# Jamali.net
KiCad netlist of a schematic drawn in Altium Designer
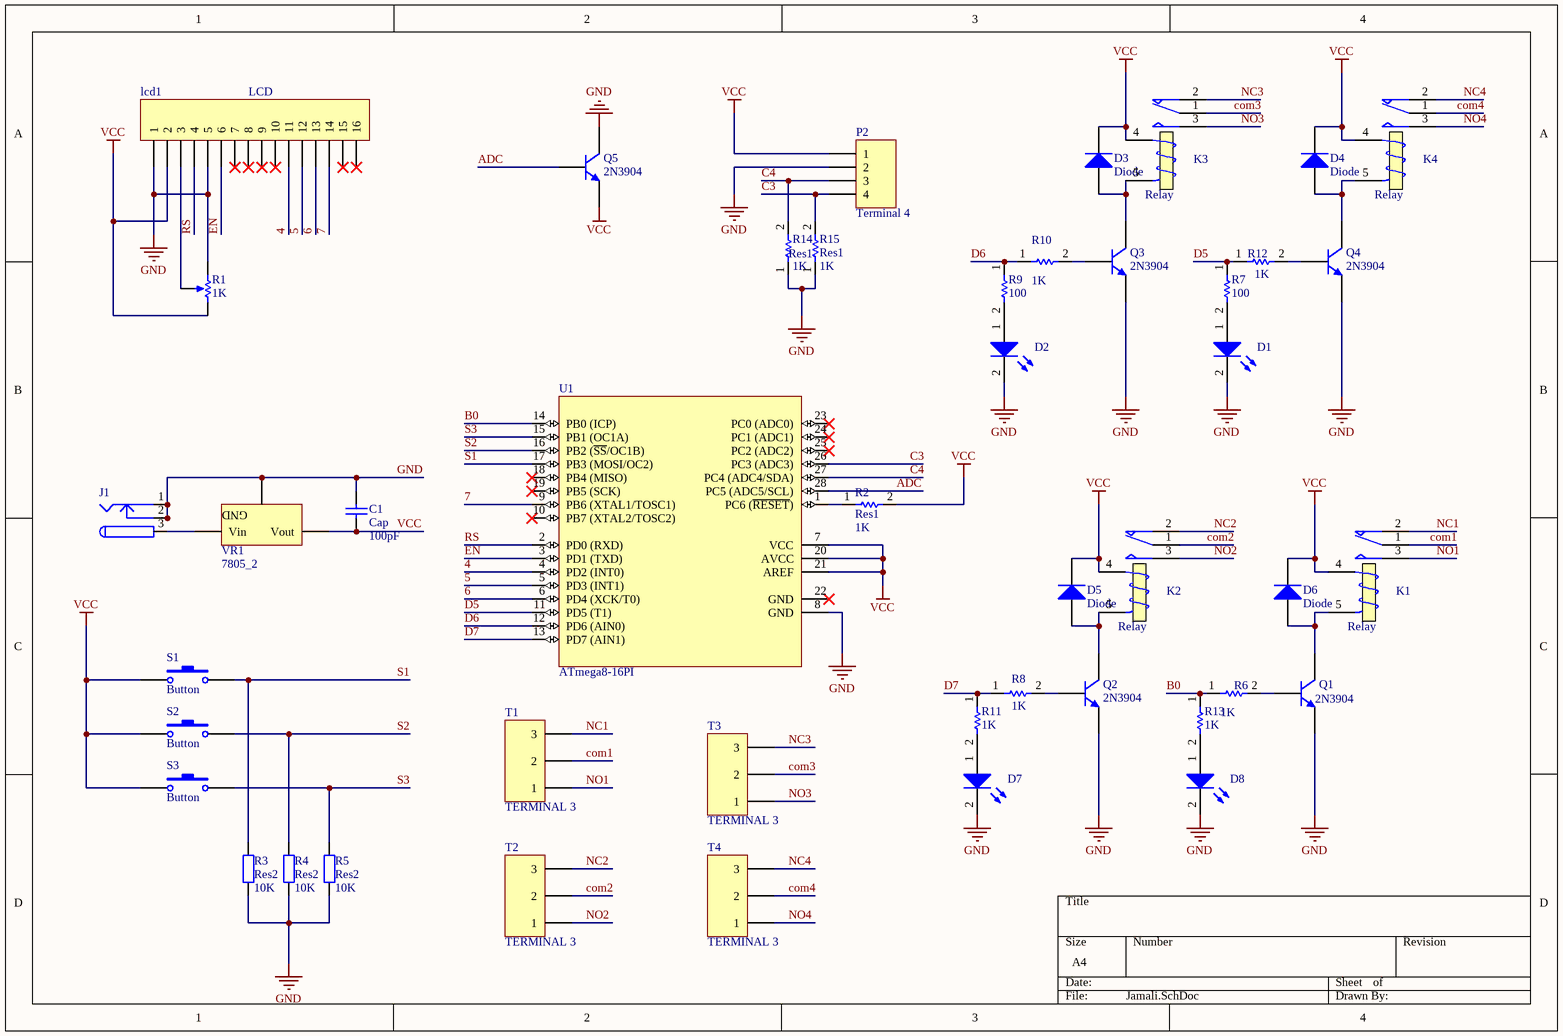
[diagram p0: Jamali.SchDoc]

(export (version "E")
  (design (tool "Eeschema 10.0.6"))
  (components
    (comp (ref "C1")
      (value "Cap")
      (footprint "C2.5-3")
      (description "Capacitor")
      (fields (field (name "ALTIUM_VALUE") "100pF") (field (name "PUBLISHER") "Altium Limited"))
      (libsource (lib "MYLIB") (part "Cap"))
    )
    (comp (ref "D1")
      (value "LED0")
      (footprint "LED3MM")
      (description "Typical INFRARED GaAs LED")
      (fields (field (name "PUBLISHER") "Altium Limited"))
      (libsource (lib "MYLIB") (part "LED0"))
    )
    (comp (ref "D2")
      (value "LED0")
      (footprint "LED3MM")
      (description "Typical INFRARED GaAs LED")
      (fields (field (name "PUBLISHER") "Altium Limited"))
      (libsource (lib "MYLIB") (part "LED0"))
    )
    (comp (ref "D3")
      (value "Diode")
      (footprint "DO35-7")
      (fields (field (name "PUBLISHER") "Altium Limited"))
      (libsource (lib "MYLIB") (part "Diode"))
    )
    (comp (ref "D4")
      (value "Diode")
      (footprint "DO35-7")
      (fields (field (name "PUBLISHER") "Altium Limited"))
      (libsource (lib "MYLIB") (part "Diode"))
    )
    (comp (ref "D5")
      (value "Diode")
      (footprint "DO35-7")
      (fields (field (name "PUBLISHER") "Altium Limited"))
      (libsource (lib "MYLIB") (part "Diode"))
    )
    (comp (ref "D6")
      (value "Diode")
      (footprint "DO35-7")
      (fields (field (name "PUBLISHER") "Altium Limited"))
      (libsource (lib "MYLIB") (part "Diode"))
    )
    (comp (ref "D7")
      (value "LED0")
      (footprint "LED3MM")
      (description "Typical INFRARED GaAs LED")
      (fields (field (name "PUBLISHER") "Altium Limited"))
      (libsource (lib "MYLIB") (part "LED0"))
    )
    (comp (ref "D8")
      (value "LED0")
      (footprint "LED3MM")
      (description "Typical INFRARED GaAs LED")
      (fields (field (name "PUBLISHER") "Altium Limited"))
      (libsource (lib "MYLIB") (part "LED0"))
    )
    (comp (ref "J1")
      (value "~")
      (footprint "jack")
      (description "Low Voltage Power Supply Connector")
      (fields (field (name "PUBLISHER") "Altium Limited"))
      (libsource (lib "MYLIB") (part "Jack"))
    )
    (comp (ref "K1")
      (value "Relay")
      (footprint "ZF112")
      (description "SPDT Relay")
      (fields (field (name "PUBLISHER") "Altium Limited"))
      (libsource (lib "MYLIB") (part "Relay"))
    )
    (comp (ref "K2")
      (value "Relay")
      (footprint "ZF112")
      (description "SPDT Relay")
      (fields (field (name "PUBLISHER") "Altium Limited"))
      (libsource (lib "MYLIB") (part "Relay"))
    )
    (comp (ref "K3")
      (value "Relay")
      (footprint "ZF112")
      (description "SPDT Relay")
      (fields (field (name "PUBLISHER") "Altium Limited"))
      (libsource (lib "MYLIB") (part "Relay"))
    )
    (comp (ref "K4")
      (value "Relay")
      (footprint "ZF112")
      (description "SPDT Relay")
      (fields (field (name "PUBLISHER") "Altium Limited"))
      (libsource (lib "MYLIB") (part "Relay"))
    )
    (comp (ref "lcd1")
      (value "LCD")
      (footprint "TUXGR_16X2_R2")
      (fields (field (name "PUBLISHER") "Altium Limited"))
      (libsource (lib "MYLIB") (part "LCD"))
    )
    (comp (ref "P2")
      (value "Terminal 4")
      (footprint "AK500/4-H")
      (description "Header, 4-Pin")
      (fields (field (name "PUBLISHER") "Altium Limited"))
      (libsource (lib "MYLIB") (part "Terminal 4"))
    )
    (comp (ref "Q1")
      (value "2N3904")
      (footprint "TO92D")
      (description "NPN General Purpose Amplifier")
      (fields (field (name "PUBLISHER") "Altium Limited"))
      (libsource (lib "MYLIB") (part "2N3904"))
    )
    (comp (ref "Q2")
      (value "2N3904")
      (footprint "TO92D")
      (description "NPN General Purpose Amplifier")
      (fields (field (name "PUBLISHER") "Altium Limited"))
      (libsource (lib "MYLIB") (part "2N3904"))
    )
    (comp (ref "Q3")
      (value "2N3904")
      (footprint "TO92D")
      (description "NPN General Purpose Amplifier")
      (fields (field (name "PUBLISHER") "Altium Limited"))
      (libsource (lib "MYLIB") (part "2N3904"))
    )
    (comp (ref "Q4")
      (value "2N3904")
      (footprint "TO92D")
      (description "NPN General Purpose Amplifier")
      (fields (field (name "PUBLISHER") "Altium Limited"))
      (libsource (lib "MYLIB") (part "2N3904"))
    )
    (comp (ref "Q5")
      (value "2N3904")
      (footprint "TO92D")
      (description "NPN General Purpose Amplifier")
      (fields (field (name "PUBLISHER") "Altium Limited"))
      (libsource (lib "MYLIB") (part "2N3904"))
    )
    (comp (ref "R1")
      (value "1K")
      (footprint "Pot_2")
      (description "Potentiometer")
      (fields (field (name "PUBLISHER") "Altium Limited"))
      (libsource (lib "MYLIB") (part "pot_2"))
    )
    (comp (ref "R2")
      (value "Res1")
      (footprint "0204/7")
      (description "Resistor")
      (fields (field (name "ALTIUM_VALUE") "1K") (field (name "PUBLISHER") "Altium Limited"))
      (libsource (lib "MYLIB") (part "Res1"))
    )
    (comp (ref "R3")
      (value "Res2")
      (footprint "0204/7")
      (description "Resistor")
      (fields (field (name "ALTIUM_VALUE") "10K") (field (name "PUBLISHER") "Altium Limited"))
      (libsource (lib "Miscellaneous Devices") (part "Res2"))
    )
    (comp (ref "R4")
      (value "Res2")
      (footprint "0204/7")
      (description "Resistor")
      (fields (field (name "ALTIUM_VALUE") "10K") (field (name "PUBLISHER") "Altium Limited"))
      (libsource (lib "Miscellaneous Devices") (part "Res2"))
    )
    (comp (ref "R5")
      (value "Res2")
      (footprint "0204/7")
      (description "Resistor")
      (fields (field (name "ALTIUM_VALUE") "10K") (field (name "PUBLISHER") "Altium Limited"))
      (libsource (lib "Miscellaneous Devices") (part "Res2"))
    )
    (comp (ref "R6")
      (value "1K")
      (footprint "0204/7")
      (description "Resistor")
      (fields (field (name "Comment") "Res1") (field (name "PUBLISHER") "Altium Limited"))
      (libsource (lib "MYLIB") (part "Res1"))
    )
    (comp (ref "R7")
      (value "100")
      (footprint "0204/7")
      (description "Resistor")
      (fields (field (name "Comment") "Res1") (field (name "PUBLISHER") "Altium Limited"))
      (libsource (lib "MYLIB") (part "Res1"))
    )
    (comp (ref "R8")
      (value "1K")
      (footprint "0204/7")
      (description "Resistor")
      (fields (field (name "Comment") "Res1") (field (name "PUBLISHER") "Altium Limited"))
      (libsource (lib "MYLIB") (part "Res1"))
    )
    (comp (ref "R9")
      (value "100")
      (footprint "0204/7")
      (description "Resistor")
      (fields (field (name "Comment") "Res1") (field (name "PUBLISHER") "Altium Limited"))
      (libsource (lib "MYLIB") (part "Res1"))
    )
    (comp (ref "R10")
      (value "1K")
      (footprint "0204/7")
      (description "Resistor")
      (fields (field (name "Comment") "Res1") (field (name "PUBLISHER") "Altium Limited"))
      (libsource (lib "MYLIB") (part "Res1"))
    )
    (comp (ref "R11")
      (value "1K")
      (footprint "0204/7")
      (description "Resistor")
      (fields (field (name "Comment") "Res1") (field (name "PUBLISHER") "Altium Limited"))
      (libsource (lib "MYLIB") (part "Res1"))
    )
    (comp (ref "R12")
      (value "1K")
      (footprint "0204/7")
      (description "Resistor")
      (fields (field (name "Comment") "Res1") (field (name "PUBLISHER") "Altium Limited"))
      (libsource (lib "MYLIB") (part "Res1"))
    )
    (comp (ref "R13")
      (value "1K")
      (footprint "0204/7")
      (description "Resistor")
      (fields (field (name "Comment") "Res1") (field (name "PUBLISHER") "Altium Limited"))
      (libsource (lib "MYLIB") (part "Res1"))
    )
    (comp (ref "R14")
      (value "Res1")
      (footprint "0204/7")
      (description "Resistor")
      (fields (field (name "ALTIUM_VALUE") "1K") (field (name "PUBLISHER") "Altium Limited"))
      (libsource (lib "MYLIB") (part "Res1"))
    )
    (comp (ref "R15")
      (value "Res1")
      (footprint "0204/7")
      (description "Resistor")
      (fields (field (name "ALTIUM_VALUE") "1K") (field (name "PUBLISHER") "Altium Limited"))
      (libsource (lib "MYLIB") (part "Res1"))
    )
    (comp (ref "S1")
      (value "Button")
      (footprint "B3F-10XX")
      (description "Switch")
      (fields (field (name "PUBLISHER") "Altium Limited"))
      (libsource (lib "MYLIB") (part "Button"))
    )
    (comp (ref "S2")
      (value "Button")
      (footprint "B3F-10XX")
      (description "Switch")
      (fields (field (name "PUBLISHER") "Altium Limited"))
      (libsource (lib "MYLIB") (part "Button"))
    )
    (comp (ref "S3")
      (value "Button")
      (footprint "B3F-10XX")
      (description "Switch")
      (fields (field (name "PUBLISHER") "Altium Limited"))
      (libsource (lib "MYLIB") (part "Button"))
    )
    (comp (ref "T1")
      (value "TERMINAL 3")
      (footprint "AK500/3-H")
      (fields (field (name "PUBLISHER") "Altium Limited"))
      (libsource (lib "MYLIB") (part "TERMINAL 3"))
    )
    (comp (ref "T2")
      (value "TERMINAL 3")
      (footprint "AK500/3-H")
      (fields (field (name "PUBLISHER") "Altium Limited"))
      (libsource (lib "MYLIB") (part "TERMINAL 3"))
    )
    (comp (ref "T3")
      (value "TERMINAL 3")
      (footprint "AK500/3-H")
      (fields (field (name "PUBLISHER") "Altium Limited"))
      (libsource (lib "MYLIB") (part "TERMINAL 3"))
    )
    (comp (ref "T4")
      (value "TERMINAL 3")
      (footprint "AK500/3-H")
      (fields (field (name "PUBLISHER") "Altium Limited"))
      (libsource (lib "MYLIB") (part "TERMINAL 3"))
    )
    (comp (ref "U1")
      (value "ATmega8-16PI")
      (footprint "DIL28-3")
      (description "8-Bit AVR Microcontroller with 8K Bytes of In-System Programmable Flash Memory")
      (fields (field (name "PUBLISHER") "Altium Limited"))
      (libsource (lib "MYLIB") (part "ATmega8-16PI"))
    )
    (comp (ref "VR1")
      (value "7805_2")
      (footprint "TO220H")
      (description "Voltage Regulator")
      (fields (field (name "PUBLISHER") "Altium Limited"))
      (libsource (lib "MYLIB") (part "7805_2"))
    )
  )
  (nets
    (net (code "1") (name "/4") (class "Default")
      (node (ref "U1") (pin "4") (pinfunction "PD2_(INT0)_4") (pintype "bidirectional"))
      (node (ref "lcd1") (pin "11") (pinfunction "11_11") (pintype "passive"))
    )
    (net (code "2") (name "/5") (class "Default")
      (node (ref "U1") (pin "5") (pinfunction "PD3_(INT1)_5") (pintype "bidirectional"))
      (node (ref "lcd1") (pin "12") (pinfunction "12_12") (pintype "passive"))
    )
    (net (code "3") (name "/6") (class "Default")
      (node (ref "U1") (pin "6") (pinfunction "PD4_(XCK/T0)_6") (pintype "bidirectional"))
      (node (ref "lcd1") (pin "13") (pinfunction "13_13") (pintype "passive"))
    )
    (net (code "4") (name "/7") (class "Default")
      (node (ref "U1") (pin "9") (pinfunction "PB6_(XTAL1/TOSC1)_9") (pintype "bidirectional"))
      (node (ref "lcd1") (pin "14") (pinfunction "14_14") (pintype "passive"))
    )
    (net (code "5") (name "/ADC") (class "Default")
      (node (ref "Q5") (pin "B") (pinfunction "B_B") (pintype "passive"))
      (node (ref "U1") (pin "28") (pinfunction "PC5_(ADC5/SCL)_28") (pintype "bidirectional"))
    )
    (net (code "6") (name "/B0") (class "Default")
      (node (ref "R13") (pin "1") (pinfunction "1_1") (pintype "passive"))
      (node (ref "R6") (pin "1") (pinfunction "1_1") (pintype "passive"))
      (node (ref "U1") (pin "14") (pinfunction "PB0_(ICP)_14") (pintype "bidirectional"))
    )
    (net (code "7") (name "/C3") (class "Default")
      (node (ref "P2") (pin "4") (pinfunction "4_4") (pintype "passive"))
      (node (ref "R15") (pin "2") (pinfunction "2_2") (pintype "passive"))
      (node (ref "U1") (pin "26") (pinfunction "PC3_(ADC3)_26") (pintype "bidirectional"))
    )
    (net (code "8") (name "/C4") (class "Default")
      (node (ref "P2") (pin "3") (pinfunction "3_3") (pintype "passive"))
      (node (ref "R14") (pin "2") (pinfunction "2_2") (pintype "passive"))
      (node (ref "U1") (pin "27") (pinfunction "PC4_(ADC4/SDA)_27") (pintype "bidirectional"))
    )
    (net (code "9") (name "/D5") (class "Default")
      (node (ref "R12") (pin "1") (pinfunction "1_1") (pintype "passive"))
      (node (ref "R7") (pin "1") (pinfunction "1_1") (pintype "passive"))
      (node (ref "U1") (pin "11") (pinfunction "PD5_(T1)_11") (pintype "bidirectional"))
    )
    (net (code "10") (name "/D6") (class "Default")
      (node (ref "R10") (pin "1") (pinfunction "1_1") (pintype "passive"))
      (node (ref "R9") (pin "1") (pinfunction "1_1") (pintype "passive"))
      (node (ref "U1") (pin "12") (pinfunction "PD6_(AIN0)_12") (pintype "bidirectional"))
    )
    (net (code "11") (name "/D7") (class "Default")
      (node (ref "R11") (pin "1") (pinfunction "1_1") (pintype "passive"))
      (node (ref "R8") (pin "1") (pinfunction "1_1") (pintype "passive"))
      (node (ref "U1") (pin "13") (pinfunction "PD7_(AIN1)_13") (pintype "bidirectional"))
    )
    (net (code "12") (name "/EN") (class "Default")
      (node (ref "U1") (pin "3") (pinfunction "PD1_(TXD)_3") (pintype "bidirectional"))
      (node (ref "lcd1") (pin "6") (pinfunction "6_6") (pintype "passive"))
    )
    (net (code "13") (name "/NC1") (class "Default")
      (node (ref "K1") (pin "2") (pinfunction "NC_2") (pintype "passive"))
      (node (ref "T1") (pin "3") (pinfunction "3_3") (pintype "passive"))
    )
    (net (code "14") (name "/NC2") (class "Default")
      (node (ref "K2") (pin "2") (pinfunction "NC_2") (pintype "passive"))
      (node (ref "T2") (pin "3") (pinfunction "3_3") (pintype "passive"))
    )
    (net (code "15") (name "/NC3") (class "Default")
      (node (ref "K3") (pin "2") (pinfunction "NC_2") (pintype "passive"))
      (node (ref "T3") (pin "3") (pinfunction "3_3") (pintype "passive"))
    )
    (net (code "16") (name "/NC4") (class "Default")
      (node (ref "K4") (pin "2") (pinfunction "NC_2") (pintype "passive"))
      (node (ref "T4") (pin "3") (pinfunction "3_3") (pintype "passive"))
    )
    (net (code "17") (name "/NO1") (class "Default")
      (node (ref "K1") (pin "3") (pinfunction "NO_3") (pintype "passive"))
      (node (ref "T1") (pin "1") (pinfunction "1_1") (pintype "passive"))
    )
    (net (code "18") (name "/NO2") (class "Default")
      (node (ref "K2") (pin "3") (pinfunction "NO_3") (pintype "passive"))
      (node (ref "T2") (pin "1") (pinfunction "1_1") (pintype "passive"))
    )
    (net (code "19") (name "/NO3") (class "Default")
      (node (ref "K3") (pin "3") (pinfunction "NO_3") (pintype "passive"))
      (node (ref "T3") (pin "1") (pinfunction "1_1") (pintype "passive"))
    )
    (net (code "20") (name "/NO4") (class "Default")
      (node (ref "K4") (pin "3") (pinfunction "NO_3") (pintype "passive"))
      (node (ref "T4") (pin "1") (pinfunction "1_1") (pintype "passive"))
    )
    (net (code "21") (name "/RS") (class "Default")
      (node (ref "U1") (pin "2") (pinfunction "PD0_(RXD)_2") (pintype "bidirectional"))
      (node (ref "lcd1") (pin "4") (pinfunction "4_4") (pintype "passive"))
    )
    (net (code "22") (name "/S1") (class "Default")
      (node (ref "R3") (pin "2") (pinfunction "2_2") (pintype "passive"))
      (node (ref "S1") (pin "2") (pinfunction "2_2") (pintype "passive"))
      (node (ref "U1") (pin "17") (pinfunction "PB3_(MOSI/OC2)_17") (pintype "bidirectional"))
    )
    (net (code "23") (name "/S2") (class "Default")
      (node (ref "R4") (pin "2") (pinfunction "2_2") (pintype "passive"))
      (node (ref "S2") (pin "2") (pinfunction "2_2") (pintype "passive"))
      (node (ref "U1") (pin "16") (pinfunction "PB2_(~{SS}/OC1B)_16") (pintype "bidirectional"))
    )
    (net (code "24") (name "/S3") (class "Default")
      (node (ref "R5") (pin "2") (pinfunction "2_2") (pintype "passive"))
      (node (ref "S3") (pin "2") (pinfunction "2_2") (pintype "passive"))
      (node (ref "U1") (pin "15") (pinfunction "PB1_(OC1A)_15") (pintype "bidirectional"))
    )
    (net (code "25") (name "/com1") (class "Default")
      (node (ref "K1") (pin "1") (pinfunction "COM_1") (pintype "passive"))
      (node (ref "T1") (pin "2") (pinfunction "2_2") (pintype "passive"))
    )
    (net (code "26") (name "/com2") (class "Default")
      (node (ref "K2") (pin "1") (pinfunction "COM_1") (pintype "passive"))
      (node (ref "T2") (pin "2") (pinfunction "2_2") (pintype "passive"))
    )
    (net (code "27") (name "/com3") (class "Default")
      (node (ref "K3") (pin "1") (pinfunction "COM_1") (pintype "passive"))
      (node (ref "T3") (pin "2") (pinfunction "2_2") (pintype "passive"))
    )
    (net (code "28") (name "/com4") (class "Default")
      (node (ref "K4") (pin "1") (pinfunction "COM_1") (pintype "passive"))
      (node (ref "T4") (pin "2") (pinfunction "2_2") (pintype "passive"))
    )
    (net (code "29") (name "GND") (class "Default")
      (node (ref "C1") (pin "2") (pinfunction "2_2") (pintype "passive"))
      (node (ref "D1") (pin "2") (pinfunction "2_2") (pintype "passive"))
      (node (ref "D2") (pin "2") (pinfunction "2_2") (pintype "passive"))
      (node (ref "D7") (pin "2") (pinfunction "2_2") (pintype "passive"))
      (node (ref "D8") (pin "2") (pinfunction "2_2") (pintype "passive"))
      (node (ref "J1") (pin "1") (pinfunction "1_1") (pintype "power_in"))
      (node (ref "J1") (pin "2") (pinfunction "2_2") (pintype "power_in"))
      (node (ref "J1") (pin "3") (pinfunction "3_3") (pintype "power_in"))
      (node (ref "P2") (pin "2") (pinfunction "2_2") (pintype "passive"))
      (node (ref "Q1") (pin "E") (pinfunction "E_E") (pintype "passive"))
      (node (ref "Q2") (pin "E") (pinfunction "E_E") (pintype "passive"))
      (node (ref "Q3") (pin "E") (pinfunction "E_E") (pintype "passive"))
      (node (ref "Q4") (pin "E") (pinfunction "E_E") (pintype "passive"))
      (node (ref "Q5") (pin "C") (pinfunction "C_C") (pintype "passive"))
      (node (ref "R1") (pin "1") (pinfunction "TOP_1") (pintype "passive"))
      (node (ref "R14") (pin "1") (pinfunction "1_1") (pintype "passive"))
      (node (ref "R15") (pin "1") (pinfunction "1_1") (pintype "passive"))
      (node (ref "R3") (pin "1") (pinfunction "1_1") (pintype "passive"))
      (node (ref "R4") (pin "1") (pinfunction "1_1") (pintype "passive"))
      (node (ref "R5") (pin "1") (pinfunction "1_1") (pintype "passive"))
      (node (ref "U1") (pin "8") (pinfunction "GND_8") (pintype "power_in"))
      (node (ref "VR1") (pin "2") (pinfunction "GND_2") (pintype "passive"))
      (node (ref "lcd1") (pin "1") (pinfunction "1_1") (pintype "passive"))
      (node (ref "lcd1") (pin "5") (pinfunction "5_5") (pintype "passive"))
    )
    (net (code "30") (name "Net-(D1-Pad1)") (class "Default")
      (node (ref "D1") (pin "1") (pinfunction "1_1") (pintype "passive"))
      (node (ref "R7") (pin "2") (pinfunction "2_2") (pintype "passive"))
    )
    (net (code "31") (name "Net-(D2-Pad1)") (class "Default")
      (node (ref "D2") (pin "1") (pinfunction "1_1") (pintype "passive"))
      (node (ref "R9") (pin "2") (pinfunction "2_2") (pintype "passive"))
    )
    (net (code "32") (name "Net-(D3-A)") (class "Default")
      (node (ref "D3") (pin "1") (pinfunction "A_1") (pintype "passive"))
      (node (ref "K3") (pin "5") (pinfunction "T2_5") (pintype "passive"))
      (node (ref "Q3") (pin "C") (pinfunction "C_C") (pintype "passive"))
    )
    (net (code "33") (name "Net-(D4-A)") (class "Default")
      (node (ref "D4") (pin "1") (pinfunction "A_1") (pintype "passive"))
      (node (ref "K4") (pin "5") (pinfunction "T2_5") (pintype "passive"))
      (node (ref "Q4") (pin "C") (pinfunction "C_C") (pintype "passive"))
    )
    (net (code "34") (name "Net-(D5-A)") (class "Default")
      (node (ref "D5") (pin "1") (pinfunction "A_1") (pintype "passive"))
      (node (ref "K2") (pin "5") (pinfunction "T2_5") (pintype "passive"))
      (node (ref "Q2") (pin "C") (pinfunction "C_C") (pintype "passive"))
    )
    (net (code "35") (name "Net-(D6-A)") (class "Default")
      (node (ref "D6") (pin "1") (pinfunction "A_1") (pintype "passive"))
      (node (ref "K1") (pin "5") (pinfunction "T2_5") (pintype "passive"))
      (node (ref "Q1") (pin "C") (pinfunction "C_C") (pintype "passive"))
    )
    (net (code "36") (name "Net-(D7-Pad1)") (class "Default")
      (node (ref "D7") (pin "1") (pinfunction "1_1") (pintype "passive"))
      (node (ref "R11") (pin "2") (pinfunction "2_2") (pintype "passive"))
    )
    (net (code "37") (name "Net-(D8-Pad1)") (class "Default")
      (node (ref "D8") (pin "1") (pinfunction "1_1") (pintype "passive"))
      (node (ref "R13") (pin "2") (pinfunction "2_2") (pintype "passive"))
    )
    (net (code "38") (name "Net-(Q1-PadB)") (class "Default")
      (node (ref "Q1") (pin "B") (pinfunction "B_B") (pintype "passive"))
      (node (ref "R6") (pin "2") (pinfunction "2_2") (pintype "passive"))
    )
    (net (code "39") (name "Net-(Q2-PadB)") (class "Default")
      (node (ref "Q2") (pin "B") (pinfunction "B_B") (pintype "passive"))
      (node (ref "R8") (pin "2") (pinfunction "2_2") (pintype "passive"))
    )
    (net (code "40") (name "Net-(Q3-PadB)") (class "Default")
      (node (ref "Q3") (pin "B") (pinfunction "B_B") (pintype "passive"))
      (node (ref "R10") (pin "2") (pinfunction "2_2") (pintype "passive"))
    )
    (net (code "41") (name "Net-(Q4-PadB)") (class "Default")
      (node (ref "Q4") (pin "B") (pinfunction "B_B") (pintype "passive"))
      (node (ref "R12") (pin "2") (pinfunction "2_2") (pintype "passive"))
    )
    (net (code "42") (name "Net-(R1-TAP)") (class "Default")
      (node (ref "R1") (pin "2") (pinfunction "TAP_2") (pintype "passive"))
      (node (ref "lcd1") (pin "3") (pinfunction "3_3") (pintype "passive"))
    )
    (net (code "43") (name "Net-(U1-PC6_(~{RESET}))") (class "Default")
      (node (ref "R2") (pin "1") (pinfunction "1_1") (pintype "passive"))
      (node (ref "U1") (pin "1") (pinfunction "PC6_(~{RESET})_1") (pintype "bidirectional"))
    )
    (net (code "44") (name "Net-(VR1-Vin)") (class "Default")
      (node (ref "J1") (pin "3") (pinfunction "3_3") (pintype "power_in"))
      (node (ref "VR1") (pin "1") (pinfunction "Vin_1") (pintype "passive"))
    )
    (net (code "45") (name "VCC") (class "Default")
      (node (ref "C1") (pin "1") (pinfunction "1_1") (pintype "passive"))
      (node (ref "D3") (pin "2") (pinfunction "K_2") (pintype "passive"))
      (node (ref "D4") (pin "2") (pinfunction "K_2") (pintype "passive"))
      (node (ref "D5") (pin "2") (pinfunction "K_2") (pintype "passive"))
      (node (ref "D6") (pin "2") (pinfunction "K_2") (pintype "passive"))
      (node (ref "K1") (pin "4") (pinfunction "T1_4") (pintype "passive"))
      (node (ref "K2") (pin "4") (pinfunction "T1_4") (pintype "passive"))
      (node (ref "K3") (pin "4") (pinfunction "T1_4") (pintype "passive"))
      (node (ref "K4") (pin "4") (pinfunction "T1_4") (pintype "passive"))
      (node (ref "P2") (pin "1") (pinfunction "1_1") (pintype "passive"))
      (node (ref "Q5") (pin "E") (pinfunction "E_E") (pintype "passive"))
      (node (ref "R1") (pin "3") (pinfunction "BOT_3") (pintype "passive"))
      (node (ref "R2") (pin "2") (pinfunction "2_2") (pintype "passive"))
      (node (ref "S1") (pin "1") (pinfunction "1_1") (pintype "passive"))
      (node (ref "S2") (pin "1") (pinfunction "1_1") (pintype "passive"))
      (node (ref "S3") (pin "1") (pinfunction "1_1") (pintype "passive"))
      (node (ref "U1") (pin "20") (pinfunction "AVCC_20") (pintype "power_in"))
      (node (ref "U1") (pin "21") (pinfunction "AREF_21") (pintype "passive"))
      (node (ref "U1") (pin "7") (pinfunction "VCC_7") (pintype "power_in"))
      (node (ref "VR1") (pin "3") (pinfunction "Vout_3") (pintype "passive"))
      (node (ref "lcd1") (pin "2") (pinfunction "2_2") (pintype "passive"))
    )
    (net (code "46") (name "unconnected-(U1-GND-Pad22)") (class "Default")
      (node (ref "U1") (pin "22") (pinfunction "GND_22") (pintype "power_in+no_connect"))
    )
    (net (code "47") (name "unconnected-(U1-PB4_(MISO)-Pad18)") (class "Default")
      (node (ref "U1") (pin "18") (pinfunction "PB4_(MISO)_18") (pintype "bidirectional+no_connect"))
    )
    (net (code "48") (name "unconnected-(U1-PB5_(SCK)-Pad19)") (class "Default")
      (node (ref "U1") (pin "19") (pinfunction "PB5_(SCK)_19") (pintype "bidirectional+no_connect"))
    )
    (net (code "49") (name "unconnected-(U1-PB7_(XTAL2{slash}TOSC2)-Pad10)") (class "Default")
      (node (ref "U1") (pin "10") (pinfunction "PB7_(XTAL2/TOSC2)_10") (pintype "bidirectional+no_connect"))
    )
    (net (code "50") (name "unconnected-(U1-PC0_(ADC0)-Pad23)") (class "Default")
      (node (ref "U1") (pin "23") (pinfunction "PC0_(ADC0)_23") (pintype "bidirectional+no_connect"))
    )
    (net (code "51") (name "unconnected-(U1-PC1_(ADC1)-Pad24)") (class "Default")
      (node (ref "U1") (pin "24") (pinfunction "PC1_(ADC1)_24") (pintype "bidirectional+no_connect"))
    )
    (net (code "52") (name "unconnected-(U1-PC2_(ADC2)-Pad25)") (class "Default")
      (node (ref "U1") (pin "25") (pinfunction "PC2_(ADC2)_25") (pintype "bidirectional+no_connect"))
    )
    (net (code "53") (name "unconnected-(lcd1-Pad7)") (class "Default")
      (node (ref "lcd1") (pin "7") (pinfunction "7_7") (pintype "passive+no_connect"))
    )
    (net (code "54") (name "unconnected-(lcd1-Pad8)") (class "Default")
      (node (ref "lcd1") (pin "8") (pinfunction "8_8") (pintype "passive+no_connect"))
    )
    (net (code "55") (name "unconnected-(lcd1-Pad9)") (class "Default")
      (node (ref "lcd1") (pin "9") (pinfunction "9_9") (pintype "passive+no_connect"))
    )
    (net (code "56") (name "unconnected-(lcd1-Pad10)") (class "Default")
      (node (ref "lcd1") (pin "10") (pinfunction "10_10") (pintype "passive+no_connect"))
    )
    (net (code "57") (name "unconnected-(lcd1-Pad15)") (class "Default")
      (node (ref "lcd1") (pin "15") (pinfunction "15_15") (pintype "passive+no_connect"))
    )
    (net (code "58") (name "unconnected-(lcd1-Pad16)") (class "Default")
      (node (ref "lcd1") (pin "16") (pinfunction "16_16") (pintype "passive+no_connect"))
    )
  )
)
